# SMDv2.net
KiCad netlist of a schematic drawn in EAGLE
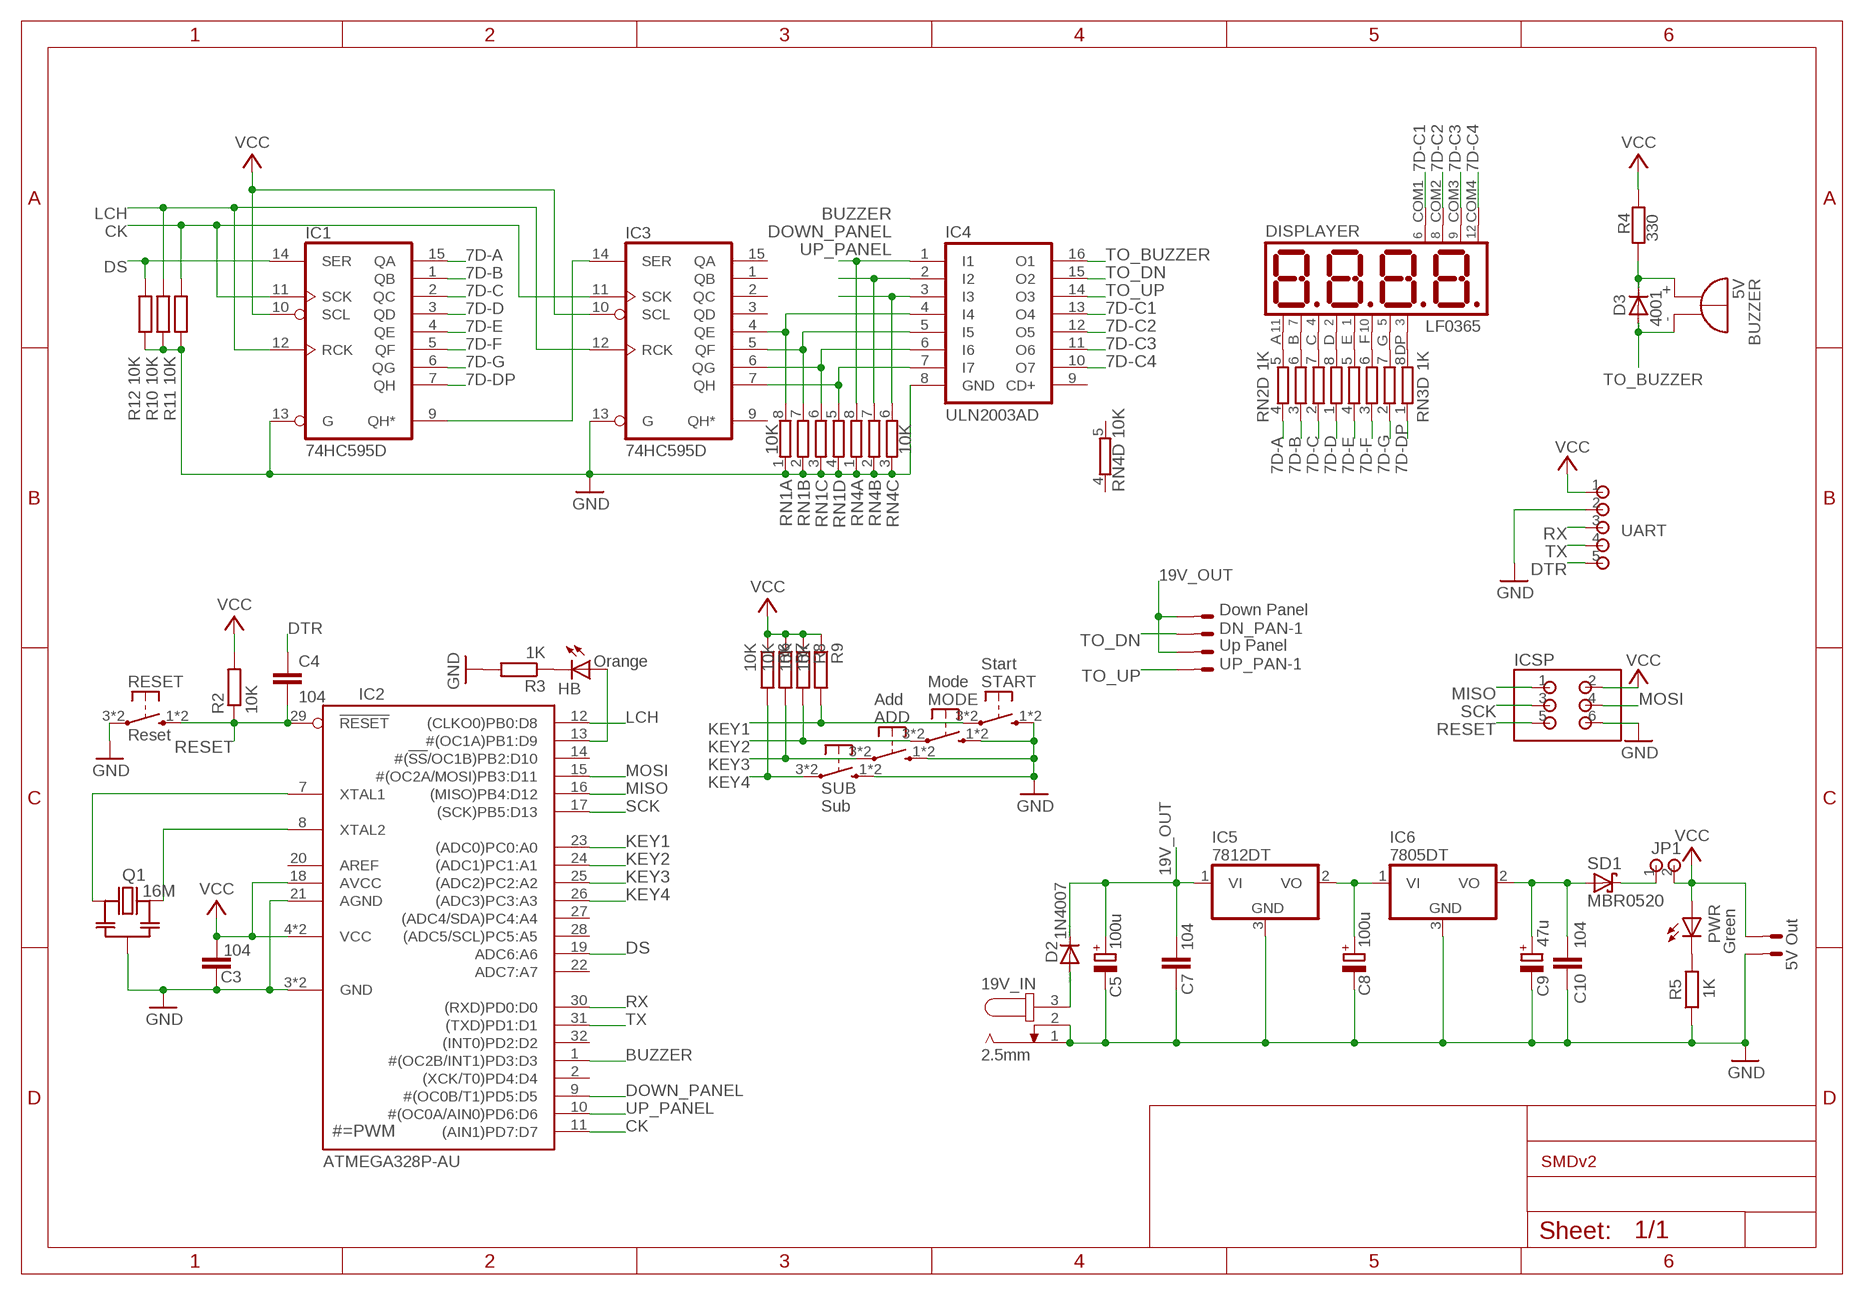
[diagram p0: schematic, sheet 1]

(export (version "E")
  (design (tool "Eeschema 10.0.6"))
  (components
    (comp (ref "5V_OUT")
      (value "5V Out")
      (footprint "eagle-import:L02P")
      (libsource (lib "eagle-import") (part "L02P"))
    )
    (comp (ref "19V_IN")
      (value "2.5mm")
      (footprint "eagle-import:SPC4078")
      (libsource (lib "eagle-import") (part "DC-JACK/2.5MM"))
    )
    (comp (ref "ADD")
      (value "Add")
      (footprint "eagle-import:SW-6_6_3.8MM")
      (libsource (lib "eagle-import") (part "SW-PUSH/663.8MM"))
    )
    (comp (ref "BUZZER")
      (value "5V")
      (footprint "eagle-import:BZ-5V")
      (libsource (lib "eagle-import") (part "BZ-5V"))
    )
    (comp (ref "C3")
      (value "104")
      (footprint "eagle-import:C0805")
      (libsource (lib "eagle-import") (part "C-EUC0805"))
    )
    (comp (ref "C4")
      (value "104")
      (footprint "eagle-import:C0805")
      (libsource (lib "eagle-import") (part "C-EUC0805"))
    )
    (comp (ref "C5")
      (value "100u")
      (footprint "eagle-import:140CLH-0810")
      (libsource (lib "eagle-import") (part "CPOL-EU140CLH-0810"))
    )
    (comp (ref "C7")
      (value "104")
      (footprint "eagle-import:C0805")
      (libsource (lib "eagle-import") (part "C-EUC0805"))
    )
    (comp (ref "C8")
      (value "100u")
      (footprint "eagle-import:SMC_C")
      (libsource (lib "eagle-import") (part "CPOL-EUSMCC"))
    )
    (comp (ref "C9")
      (value "47u")
      (footprint "eagle-import:SMC_C")
      (libsource (lib "eagle-import") (part "CPOL-EUSMCC"))
    )
    (comp (ref "C10")
      (value "104")
      (footprint "eagle-import:C0805")
      (libsource (lib "eagle-import") (part "C-EUC0805"))
    )
    (comp (ref "D2")
      (value "1N4007")
      (footprint "eagle-import:DO-214AC")
      (libsource (lib "eagle-import") (part "DIODE-DO-214AC"))
    )
    (comp (ref "D3")
      (value "4001")
      (footprint "eagle-import:DO-214AC")
      (libsource (lib "eagle-import") (part "DIODE-DO-214AC"))
    )
    (comp (ref "DISPLAYER")
      (value "LF0365")
      (footprint "eagle-import:LF036_")
      (libsource (lib "eagle-import") (part "LF0365"))
    )
    (comp (ref "DN_PAN")
      (value "Down Panel")
      (footprint "eagle-import:L02P")
      (libsource (lib "eagle-import") (part "L02P"))
    )
    (comp (ref "HB")
      (value "Orange")
      (footprint "eagle-import:CHIPLED_1206")
      (libsource (lib "eagle-import") (part "LEDCHIPLED_1206"))
    )
    (comp (ref "IC1")
      (value "74HC595D")
      (footprint "eagle-import:SO16")
      (libsource (lib "eagle-import") (part "74595DHC"))
    )
    (comp (ref "IC2")
      (value "ATMEGA328P-AU")
      (footprint "eagle-import:TQFP32")
      (libsource (lib "eagle-import") (part "ATMEGA328P-AU"))
    )
    (comp (ref "IC3")
      (value "74HC595D")
      (footprint "eagle-import:SO16")
      (libsource (lib "eagle-import") (part "74595DHC"))
    )
    (comp (ref "IC4")
      (value "ULN2003AD")
      (footprint "eagle-import:SO16")
      (libsource (lib "eagle-import") (part "ULN2003AD"))
    )
    (comp (ref "IC5")
      (value "7812DT")
      (footprint "eagle-import:TO252")
      (libsource (lib "eagle-import") (part "78DT12"))
    )
    (comp (ref "IC6")
      (value "7805DT")
      (footprint "eagle-import:TO252")
      (libsource (lib "eagle-import") (part "78DT05"))
    )
    (comp (ref "ICSP")
      (value "PIN-2X3/DIP")
      (footprint "eagle-import:DIP-2.54-2X3")
      (libsource (lib "eagle-import") (part "PIN-2X3/DIP"))
    )
    (comp (ref "JP1")
      (value "PIN-1X2-2.54")
      (footprint "eagle-import:DIP-2.54-1X2")
      (libsource (lib "eagle-import") (part "PIN-1X2-2.54"))
    )
    (comp (ref "MODE")
      (value "Mode")
      (footprint "eagle-import:SW-6_6_3.8MM")
      (libsource (lib "eagle-import") (part "SW-PUSH/663.8MM"))
    )
    (comp (ref "PWR")
      (value "Green")
      (footprint "eagle-import:CHIPLED_1206")
      (libsource (lib "eagle-import") (part "LEDCHIPLED_1206"))
    )
    (comp (ref "Q1")
      (value "16M")
      (footprint "eagle-import:CSTCE")
      (libsource (lib "eagle-import") (part "CERMOSCILL-CSTCE"))
    )
    (comp (ref "R2")
      (value "10K")
      (footprint "eagle-import:R0805")
      (libsource (lib "eagle-import") (part "R-EU_R0805"))
    )
    (comp (ref "R3")
      (value "1K")
      (footprint "eagle-import:R0805")
      (libsource (lib "eagle-import") (part "R-EU_R0805"))
    )
    (comp (ref "R4")
      (value "330")
      (footprint "eagle-import:R0805")
      (libsource (lib "eagle-import") (part "R-EU_R0805"))
    )
    (comp (ref "R5")
      (value "1K")
      (footprint "eagle-import:R0805")
      (libsource (lib "eagle-import") (part "R-EU_R0805"))
    )
    (comp (ref "R6")
      (value "10K")
      (footprint "eagle-import:R0805")
      (libsource (lib "eagle-import") (part "R-EU_R0805"))
    )
    (comp (ref "R7")
      (value "10K")
      (footprint "eagle-import:R0805")
      (libsource (lib "eagle-import") (part "R-EU_R0805"))
    )
    (comp (ref "R8")
      (value "10K")
      (footprint "eagle-import:R0805")
      (libsource (lib "eagle-import") (part "R-EU_R0805"))
    )
    (comp (ref "R9")
      (value "10K")
      (footprint "eagle-import:R0805")
      (libsource (lib "eagle-import") (part "R-EU_R0805"))
    )
    (comp (ref "R10")
      (value "10K")
      (footprint "eagle-import:R0805")
      (libsource (lib "eagle-import") (part "R-EU_R0805"))
    )
    (comp (ref "R11")
      (value "10K")
      (footprint "eagle-import:R0805")
      (libsource (lib "eagle-import") (part "R-EU_R0805"))
    )
    (comp (ref "R12")
      (value "10K")
      (footprint "eagle-import:R0805")
      (libsource (lib "eagle-import") (part "R-EU_R0805"))
    )
    (comp (ref "RESET")
      (value "Reset")
      (footprint "eagle-import:SW-4_4_3.8MM")
      (libsource (lib "eagle-import") (part "SW-PUSH/443.8MM"))
    )
    (comp (ref "RN1")
      (value "10K")
      (footprint "eagle-import:CAY16")
      (libsource (lib "eagle-import") (part "RN4R-CAY16"))
    )
    (comp (ref "RN2")
      (value "1K")
      (footprint "eagle-import:CAY16")
      (libsource (lib "eagle-import") (part "RN4R-CAY16"))
    )
    (comp (ref "RN3")
      (value "1K")
      (footprint "eagle-import:CAY16")
      (libsource (lib "eagle-import") (part "RN4R-CAY16"))
    )
    (comp (ref "RN4")
      (value "10K")
      (footprint "eagle-import:CAY16")
      (libsource (lib "eagle-import") (part "RN4R-CAY16"))
    )
    (comp (ref "SD1")
      (value "MBR0520")
      (footprint "eagle-import:SOD123")
      (libsource (lib "eagle-import") (part "SCHOTTKY"))
    )
    (comp (ref "START")
      (value "Start")
      (footprint "eagle-import:SW-6_6_3.8MM")
      (libsource (lib "eagle-import") (part "SW-PUSH/663.8MM"))
    )
    (comp (ref "SUB")
      (value "Sub")
      (footprint "eagle-import:SW-6_6_3.8MM")
      (libsource (lib "eagle-import") (part "SW-PUSH/663.8MM"))
    )
    (comp (ref "UART")
      (value "PIN-1X5-2.54")
      (footprint "eagle-import:DIP-2.54-1X5")
      (libsource (lib "eagle-import") (part "PIN-1X5-2.54"))
    )
    (comp (ref "UP_PAN")
      (value "Up Panel")
      (footprint "eagle-import:L02P")
      (libsource (lib "eagle-import") (part "L02P"))
    )
  )
  (nets
    (net (code "1") (name "/7D-A") (class "Default")
      (node (ref "IC1") (pin "15") (pinfunction "QA_15") (pintype "tri_state"))
      (node (ref "RN2") (pin "4") (pinfunction "1_4") (pintype "passive"))
    )
    (net (code "2") (name "/7D-B") (class "Default")
      (node (ref "IC1") (pin "1") (pinfunction "QB_1") (pintype "tri_state"))
      (node (ref "RN2") (pin "3") (pinfunction "1_3") (pintype "passive"))
    )
    (net (code "3") (name "/7D-C") (class "Default")
      (node (ref "IC1") (pin "2") (pinfunction "QC_2") (pintype "tri_state"))
      (node (ref "RN2") (pin "2") (pinfunction "1_2") (pintype "passive"))
    )
    (net (code "4") (name "/7D-C1") (class "Default")
      (node (ref "DISPLAYER") (pin "COM1") (pinfunction "COM1_COM1") (pintype "passive"))
      (node (ref "IC4") (pin "13") (pinfunction "O4_13") (pintype "open_collector"))
    )
    (net (code "5") (name "/7D-C2") (class "Default")
      (node (ref "DISPLAYER") (pin "COM2") (pinfunction "COM2_COM2") (pintype "passive"))
      (node (ref "IC4") (pin "12") (pinfunction "O5_12") (pintype "open_collector"))
    )
    (net (code "6") (name "/7D-C3") (class "Default")
      (node (ref "DISPLAYER") (pin "COM3") (pinfunction "COM3_COM3") (pintype "passive"))
      (node (ref "IC4") (pin "11") (pinfunction "O6_11") (pintype "open_collector"))
    )
    (net (code "7") (name "/7D-C4") (class "Default")
      (node (ref "DISPLAYER") (pin "COM4") (pinfunction "COM4_COM4") (pintype "passive"))
      (node (ref "IC4") (pin "10") (pinfunction "O7_10") (pintype "open_collector"))
    )
    (net (code "8") (name "/7D-D") (class "Default")
      (node (ref "IC1") (pin "3") (pinfunction "QD_3") (pintype "tri_state"))
      (node (ref "RN2") (pin "1") (pinfunction "1_1") (pintype "passive"))
    )
    (net (code "9") (name "/7D-DP") (class "Default")
      (node (ref "IC1") (pin "7") (pinfunction "QH_7") (pintype "tri_state"))
      (node (ref "RN3") (pin "1") (pinfunction "1_1") (pintype "passive"))
    )
    (net (code "10") (name "/7D-E") (class "Default")
      (node (ref "IC1") (pin "4") (pinfunction "QE_4") (pintype "tri_state"))
      (node (ref "RN3") (pin "4") (pinfunction "1_4") (pintype "passive"))
    )
    (net (code "11") (name "/7D-F") (class "Default")
      (node (ref "IC1") (pin "5") (pinfunction "QF_5") (pintype "tri_state"))
      (node (ref "RN3") (pin "3") (pinfunction "1_3") (pintype "passive"))
    )
    (net (code "12") (name "/7D-G") (class "Default")
      (node (ref "IC1") (pin "6") (pinfunction "QG_6") (pintype "tri_state"))
      (node (ref "RN3") (pin "2") (pinfunction "1_2") (pintype "passive"))
    )
    (net (code "13") (name "/19V_OUT") (class "Default")
      (node (ref "C5") (pin "+") (pinfunction "+_+") (pintype "passive"))
      (node (ref "C7") (pin "1") (pinfunction "1_1") (pintype "passive"))
      (node (ref "D2") (pin "C") (pinfunction "C_C") (pintype "passive"))
      (node (ref "DN_PAN") (pin "2") (pinfunction "S_2") (pintype "passive"))
      (node (ref "IC5") (pin "1") (pinfunction "VI_1") (pintype "input"))
      (node (ref "UP_PAN") (pin "2") (pinfunction "S_2") (pintype "passive"))
    )
    (net (code "14") (name "/BUZZER") (class "Default")
      (node (ref "IC2") (pin "1") (pinfunction "#(OC2B/INT1)PD3:D3_1") (pintype "bidirectional"))
      (node (ref "IC4") (pin "1") (pinfunction "I1_1") (pintype "input"))
      (node (ref "RN4") (pin "8") (pinfunction "2_8") (pintype "passive"))
    )
    (net (code "15") (name "/CK") (class "Default")
      (node (ref "IC1") (pin "11") (pinfunction "SCK_11") (pintype "input"))
      (node (ref "IC2") (pin "11") (pinfunction "(AIN1)PD7:D7_11") (pintype "bidirectional"))
      (node (ref "IC3") (pin "11") (pinfunction "SCK_11") (pintype "input"))
      (node (ref "R11") (pin "2") (pinfunction "2_2") (pintype "passive"))
    )
    (net (code "16") (name "/DOWN_PANEL") (class "Default")
      (node (ref "IC2") (pin "9") (pinfunction "#(OC0B/T1)PD5:D5_9") (pintype "bidirectional"))
      (node (ref "IC4") (pin "2") (pinfunction "I2_2") (pintype "input"))
      (node (ref "RN4") (pin "7") (pinfunction "2_7") (pintype "passive"))
    )
    (net (code "17") (name "/DS") (class "Default")
      (node (ref "IC1") (pin "14") (pinfunction "SER_14") (pintype "input"))
      (node (ref "IC2") (pin "19") (pinfunction "ADC6:A6_19") (pintype "bidirectional"))
      (node (ref "R12") (pin "2") (pinfunction "2_2") (pintype "passive"))
    )
    (net (code "18") (name "/DTR") (class "Default")
      (node (ref "C4") (pin "1") (pinfunction "1_1") (pintype "passive"))
      (node (ref "UART") (pin "5") (pinfunction "5_5") (pintype "passive"))
    )
    (net (code "19") (name "/KEY1") (class "Default")
      (node (ref "IC2") (pin "23") (pinfunction "(ADC0)PC0:A0_23") (pintype "bidirectional"))
      (node (ref "R9") (pin "2") (pinfunction "2_2") (pintype "passive"))
      (node (ref "START") (pin "3") (pinfunction "P_3") (pintype "passive"))
      (node (ref "START") (pin "4") (pinfunction "P_4") (pintype "passive"))
    )
    (net (code "20") (name "/KEY2") (class "Default")
      (node (ref "IC2") (pin "24") (pinfunction "(ADC1)PC1:A1_24") (pintype "bidirectional"))
      (node (ref "MODE") (pin "3") (pinfunction "P_3") (pintype "passive"))
      (node (ref "MODE") (pin "4") (pinfunction "P_4") (pintype "passive"))
      (node (ref "R8") (pin "2") (pinfunction "2_2") (pintype "passive"))
    )
    (net (code "21") (name "/KEY3") (class "Default")
      (node (ref "ADD") (pin "3") (pinfunction "P_3") (pintype "passive"))
      (node (ref "ADD") (pin "4") (pinfunction "P_4") (pintype "passive"))
      (node (ref "IC2") (pin "25") (pinfunction "(ADC2)PC2:A2_25") (pintype "bidirectional"))
      (node (ref "R7") (pin "2") (pinfunction "2_2") (pintype "passive"))
    )
    (net (code "22") (name "/KEY4") (class "Default")
      (node (ref "IC2") (pin "26") (pinfunction "(ADC3)PC3:A3_26") (pintype "bidirectional"))
      (node (ref "R6") (pin "2") (pinfunction "2_2") (pintype "passive"))
      (node (ref "SUB") (pin "3") (pinfunction "P_3") (pintype "passive"))
      (node (ref "SUB") (pin "4") (pinfunction "P_4") (pintype "passive"))
    )
    (net (code "23") (name "/LCH") (class "Default")
      (node (ref "IC1") (pin "12") (pinfunction "RCK_12") (pintype "input"))
      (node (ref "IC2") (pin "12") (pinfunction "(CLKO0)PB0:D8_12") (pintype "bidirectional"))
      (node (ref "IC3") (pin "12") (pinfunction "RCK_12") (pintype "input"))
      (node (ref "R10") (pin "2") (pinfunction "2_2") (pintype "passive"))
    )
    (net (code "24") (name "/MISO") (class "Default")
      (node (ref "IC2") (pin "16") (pinfunction "(MISO)PB4:D12_16") (pintype "bidirectional"))
      (node (ref "ICSP") (pin "1") (pinfunction "1_1") (pintype "passive"))
    )
    (net (code "25") (name "/MOSI") (class "Default")
      (node (ref "IC2") (pin "15") (pinfunction "#(OC2A/MOSI)PB3:D11_15") (pintype "bidirectional"))
      (node (ref "ICSP") (pin "4") (pinfunction "4_4") (pintype "passive"))
    )
    (net (code "26") (name "/RESET") (class "Default")
      (node (ref "C4") (pin "2") (pinfunction "2_2") (pintype "passive"))
      (node (ref "IC2") (pin "29") (pinfunction "~{RESET}_29") (pintype "input"))
      (node (ref "ICSP") (pin "5") (pinfunction "5_5") (pintype "passive"))
      (node (ref "R2") (pin "1") (pinfunction "1_1") (pintype "passive"))
      (node (ref "RESET") (pin "1") (pinfunction "S_1") (pintype "passive"))
      (node (ref "RESET") (pin "2") (pinfunction "S_2") (pintype "passive"))
    )
    (net (code "27") (name "/RX") (class "Default")
      (node (ref "IC2") (pin "30") (pinfunction "(RXD)PD0:D0_30") (pintype "bidirectional"))
      (node (ref "UART") (pin "3") (pinfunction "3_3") (pintype "passive"))
    )
    (net (code "28") (name "/SCK") (class "Default")
      (node (ref "IC2") (pin "17") (pinfunction "(SCK)PB5:D13_17") (pintype "bidirectional"))
      (node (ref "ICSP") (pin "3") (pinfunction "3_3") (pintype "passive"))
    )
    (net (code "29") (name "/TO_BUZZER") (class "Default")
      (node (ref "BUZZER") (pin "-") (pinfunction "-_-") (pintype "passive"))
      (node (ref "D3") (pin "A") (pinfunction "A_A") (pintype "passive"))
      (node (ref "IC4") (pin "16") (pinfunction "O1_16") (pintype "open_collector"))
    )
    (net (code "30") (name "/TO_DN") (class "Default")
      (node (ref "DN_PAN") (pin "1") (pinfunction "S_1") (pintype "passive"))
      (node (ref "IC4") (pin "15") (pinfunction "O2_15") (pintype "open_collector"))
    )
    (net (code "31") (name "/TO_UP") (class "Default")
      (node (ref "IC4") (pin "14") (pinfunction "O3_14") (pintype "open_collector"))
      (node (ref "UP_PAN") (pin "1") (pinfunction "S_1") (pintype "passive"))
    )
    (net (code "32") (name "/TX") (class "Default")
      (node (ref "IC2") (pin "31") (pinfunction "(TXD)PD1:D1_31") (pintype "bidirectional"))
      (node (ref "UART") (pin "4") (pinfunction "4_4") (pintype "passive"))
    )
    (net (code "33") (name "/UP_PANEL") (class "Default")
      (node (ref "IC2") (pin "10") (pinfunction "#(OC0A/AIN0)PD6:D6_10") (pintype "bidirectional"))
      (node (ref "IC4") (pin "3") (pinfunction "I3_3") (pintype "input"))
      (node (ref "RN4") (pin "6") (pinfunction "2_6") (pintype "passive"))
    )
    (net (code "34") (name "GND") (class "Default")
      (node (ref "19V_IN") (pin "1") (pinfunction "1_1") (pintype "passive"))
      (node (ref "19V_IN") (pin "2") (pinfunction "2_2") (pintype "passive"))
      (node (ref "5V_OUT") (pin "1") (pinfunction "S_1") (pintype "passive"))
      (node (ref "ADD") (pin "1") (pinfunction "S_1") (pintype "passive"))
      (node (ref "ADD") (pin "2") (pinfunction "S_2") (pintype "passive"))
      (node (ref "C10") (pin "2") (pinfunction "2_2") (pintype "passive"))
      (node (ref "C3") (pin "1") (pinfunction "1_1") (pintype "passive"))
      (node (ref "C5") (pin "-") (pinfunction "-_-") (pintype "passive"))
      (node (ref "C7") (pin "2") (pinfunction "2_2") (pintype "passive"))
      (node (ref "C8") (pin "-") (pinfunction "-_-") (pintype "passive"))
      (node (ref "C9") (pin "-") (pinfunction "-_-") (pintype "passive"))
      (node (ref "IC1") (pin "13") (pinfunction "G_13") (pintype "input"))
      (node (ref "IC2") (pin "21") (pinfunction "AGND_21") (pintype "passive"))
      (node (ref "IC2") (pin "3") (pinfunction "GND_3") (pintype "power_in"))
      (node (ref "IC2") (pin "5") (pinfunction "GND_5") (pintype "power_in"))
      (node (ref "IC3") (pin "13") (pinfunction "G_13") (pintype "input"))
      (node (ref "IC4") (pin "8") (pinfunction "GND_8") (pintype "power_in"))
      (node (ref "IC5") (pin "3") (pinfunction "GND_3") (pintype "passive"))
      (node (ref "IC6") (pin "3") (pinfunction "GND_3") (pintype "passive"))
      (node (ref "ICSP") (pin "6") (pinfunction "6_6") (pintype "passive"))
      (node (ref "MODE") (pin "1") (pinfunction "S_1") (pintype "passive"))
      (node (ref "MODE") (pin "2") (pinfunction "S_2") (pintype "passive"))
      (node (ref "Q1") (pin "2") (pinfunction "GND_2") (pintype "bidirectional"))
      (node (ref "R10") (pin "1") (pinfunction "1_1") (pintype "passive"))
      (node (ref "R11") (pin "1") (pinfunction "1_1") (pintype "passive"))
      (node (ref "R12") (pin "1") (pinfunction "1_1") (pintype "passive"))
      (node (ref "R3") (pin "2") (pinfunction "2_2") (pintype "passive"))
      (node (ref "R5") (pin "1") (pinfunction "1_1") (pintype "passive"))
      (node (ref "RESET") (pin "3") (pinfunction "P_3") (pintype "passive"))
      (node (ref "RESET") (pin "4") (pinfunction "P_4") (pintype "passive"))
      (node (ref "RN1") (pin "1") (pinfunction "1_1") (pintype "passive"))
      (node (ref "RN1") (pin "2") (pinfunction "1_2") (pintype "passive"))
      (node (ref "RN1") (pin "3") (pinfunction "1_3") (pintype "passive"))
      (node (ref "RN1") (pin "4") (pinfunction "1_4") (pintype "passive"))
      (node (ref "RN4") (pin "1") (pinfunction "1_1") (pintype "passive"))
      (node (ref "RN4") (pin "2") (pinfunction "1_2") (pintype "passive"))
      (node (ref "RN4") (pin "3") (pinfunction "1_3") (pintype "passive"))
      (node (ref "START") (pin "1") (pinfunction "S_1") (pintype "passive"))
      (node (ref "START") (pin "2") (pinfunction "S_2") (pintype "passive"))
      (node (ref "SUB") (pin "1") (pinfunction "S_1") (pintype "passive"))
      (node (ref "SUB") (pin "2") (pinfunction "S_2") (pintype "passive"))
      (node (ref "UART") (pin "2") (pinfunction "2_2") (pintype "passive"))
    )
    (net (code "35") (name "Net-(19V_IN-Pad3)") (class "Default")
      (node (ref "19V_IN") (pin "3") (pinfunction "3_3") (pintype "passive"))
      (node (ref "D2") (pin "A") (pinfunction "A_A") (pintype "passive"))
    )
    (net (code "36") (name "Net-(BUZZER-Pad+)") (class "Default")
      (node (ref "BUZZER") (pin "+") (pinfunction "+_+") (pintype "passive"))
      (node (ref "D3") (pin "C") (pinfunction "C_C") (pintype "passive"))
      (node (ref "R4") (pin "1") (pinfunction "1_1") (pintype "passive"))
    )
    (net (code "37") (name "Net-(HB-PadC)") (class "Default")
      (node (ref "HB") (pin "C") (pinfunction "C_C") (pintype "passive"))
      (node (ref "R3") (pin "1") (pinfunction "1_1") (pintype "passive"))
    )
    (net (code "38") (name "Net-(IC1A-QH*)") (class "Default")
      (node (ref "IC1") (pin "9") (pinfunction "QH*_9") (pintype "tri_state"))
      (node (ref "IC3") (pin "14") (pinfunction "SER_14") (pintype "input"))
    )
    (net (code "39") (name "Net-(IC2-#(OC1A)PB1:D9)") (class "Default")
      (node (ref "HB") (pin "A") (pinfunction "A_A") (pintype "passive"))
      (node (ref "IC2") (pin "13") (pinfunction "#(OC1A)PB1:D9_13") (pintype "bidirectional"))
    )
    (net (code "40") (name "Net-(IC2-XTAL1)") (class "Default")
      (node (ref "IC2") (pin "7") (pinfunction "XTAL1_7") (pintype "bidirectional"))
      (node (ref "Q1") (pin "1") (pinfunction "IN_1") (pintype "bidirectional"))
    )
    (net (code "41") (name "Net-(IC2-XTAL2)") (class "Default")
      (node (ref "IC2") (pin "8") (pinfunction "XTAL2_8") (pintype "bidirectional"))
      (node (ref "Q1") (pin "3") (pinfunction "OUT_3") (pintype "bidirectional"))
    )
    (net (code "42") (name "Net-(IC3A-QE)") (class "Default")
      (node (ref "IC3") (pin "4") (pinfunction "QE_4") (pintype "tri_state"))
      (node (ref "IC4") (pin "4") (pinfunction "I4_4") (pintype "input"))
      (node (ref "RN1") (pin "8") (pinfunction "2_8") (pintype "passive"))
    )
    (net (code "43") (name "Net-(IC3A-QF)") (class "Default")
      (node (ref "IC3") (pin "5") (pinfunction "QF_5") (pintype "tri_state"))
      (node (ref "IC4") (pin "5") (pinfunction "I5_5") (pintype "input"))
      (node (ref "RN1") (pin "7") (pinfunction "2_7") (pintype "passive"))
    )
    (net (code "44") (name "Net-(IC3A-QG)") (class "Default")
      (node (ref "IC3") (pin "6") (pinfunction "QG_6") (pintype "tri_state"))
      (node (ref "IC4") (pin "6") (pinfunction "I6_6") (pintype "input"))
      (node (ref "RN1") (pin "6") (pinfunction "2_6") (pintype "passive"))
    )
    (net (code "45") (name "Net-(IC3A-QH)") (class "Default")
      (node (ref "IC3") (pin "7") (pinfunction "QH_7") (pintype "tri_state"))
      (node (ref "IC4") (pin "7") (pinfunction "I7_7") (pintype "input"))
      (node (ref "RN1") (pin "5") (pinfunction "2_5") (pintype "passive"))
    )
    (net (code "46") (name "Net-(IC5-VO)") (class "Default")
      (node (ref "C8") (pin "+") (pinfunction "+_+") (pintype "passive"))
      (node (ref "IC5") (pin "2") (pinfunction "VO_2") (pintype "passive"))
      (node (ref "IC6") (pin "1") (pinfunction "VI_1") (pintype "input"))
    )
    (net (code "47") (name "Net-(IC6-VO)") (class "Default")
      (node (ref "C10") (pin "1") (pinfunction "1_1") (pintype "passive"))
      (node (ref "C9") (pin "+") (pinfunction "+_+") (pintype "passive"))
      (node (ref "IC6") (pin "2") (pinfunction "VO_2") (pintype "passive"))
      (node (ref "SD1") (pin "A") (pinfunction "A_A") (pintype "passive"))
    )
    (net (code "48") (name "Net-(JP1-Pad1)") (class "Default")
      (node (ref "JP1") (pin "1") (pinfunction "1_1") (pintype "passive"))
      (node (ref "SD1") (pin "K") (pinfunction "K_K") (pintype "passive"))
    )
    (net (code "49") (name "Net-(PWR-PadC)") (class "Default")
      (node (ref "PWR") (pin "C") (pinfunction "C_C") (pintype "passive"))
      (node (ref "R5") (pin "2") (pinfunction "2_2") (pintype "passive"))
    )
    (net (code "50") (name "Net-(RN2A-2)") (class "Default")
      (node (ref "DISPLAYER") (pin "D") (pinfunction "D_D") (pintype "input"))
      (node (ref "RN2") (pin "8") (pinfunction "2_8") (pintype "passive"))
    )
    (net (code "51") (name "Net-(RN2B-2)") (class "Default")
      (node (ref "DISPLAYER") (pin "C") (pinfunction "C_C") (pintype "input"))
      (node (ref "RN2") (pin "7") (pinfunction "2_7") (pintype "passive"))
    )
    (net (code "52") (name "Net-(RN2C-2)") (class "Default")
      (node (ref "DISPLAYER") (pin "B") (pinfunction "B_B") (pintype "input"))
      (node (ref "RN2") (pin "6") (pinfunction "2_6") (pintype "passive"))
    )
    (net (code "53") (name "Net-(RN2D-2)") (class "Default")
      (node (ref "DISPLAYER") (pin "A") (pinfunction "A_A") (pintype "input"))
      (node (ref "RN2") (pin "5") (pinfunction "2_5") (pintype "passive"))
    )
    (net (code "54") (name "Net-(RN3A-2)") (class "Default")
      (node (ref "DISPLAYER") (pin "DP") (pinfunction "DP_DP") (pintype "input"))
      (node (ref "RN3") (pin "8") (pinfunction "2_8") (pintype "passive"))
    )
    (net (code "55") (name "Net-(RN3B-2)") (class "Default")
      (node (ref "DISPLAYER") (pin "G") (pinfunction "G_G") (pintype "input"))
      (node (ref "RN3") (pin "7") (pinfunction "2_7") (pintype "passive"))
    )
    (net (code "56") (name "Net-(RN3C-2)") (class "Default")
      (node (ref "DISPLAYER") (pin "F") (pinfunction "F_F") (pintype "input"))
      (node (ref "RN3") (pin "6") (pinfunction "2_6") (pintype "passive"))
    )
    (net (code "57") (name "Net-(RN3D-2)") (class "Default")
      (node (ref "DISPLAYER") (pin "E") (pinfunction "E_E") (pintype "input"))
      (node (ref "RN3") (pin "5") (pinfunction "2_5") (pintype "passive"))
    )
    (net (code "58") (name "VCC") (class "Default")
      (node (ref "5V_OUT") (pin "2") (pinfunction "S_2") (pintype "passive"))
      (node (ref "C3") (pin "2") (pinfunction "2_2") (pintype "passive"))
      (node (ref "IC1") (pin "10") (pinfunction "SCL_10") (pintype "input"))
      (node (ref "IC2") (pin "18") (pinfunction "AVCC_18") (pintype "passive"))
      (node (ref "IC2") (pin "4") (pinfunction "VCC_4") (pintype "power_in"))
      (node (ref "IC2") (pin "6") (pinfunction "VCC_6") (pintype "power_in"))
      (node (ref "IC3") (pin "10") (pinfunction "SCL_10") (pintype "input"))
      (node (ref "ICSP") (pin "2") (pinfunction "2_2") (pintype "passive"))
      (node (ref "JP1") (pin "2") (pinfunction "2_2") (pintype "passive"))
      (node (ref "PWR") (pin "A") (pinfunction "A_A") (pintype "passive"))
      (node (ref "R2") (pin "2") (pinfunction "2_2") (pintype "passive"))
      (node (ref "R4") (pin "2") (pinfunction "2_2") (pintype "passive"))
      (node (ref "R6") (pin "1") (pinfunction "1_1") (pintype "passive"))
      (node (ref "R7") (pin "1") (pinfunction "1_1") (pintype "passive"))
      (node (ref "R8") (pin "1") (pinfunction "1_1") (pintype "passive"))
      (node (ref "R9") (pin "1") (pinfunction "1_1") (pintype "passive"))
      (node (ref "UART") (pin "1") (pinfunction "1_1") (pintype "passive"))
    )
    (net (code "59") (name "unconnected-(IC2-#(~{SS}{slash}OC1B)PB2:D10-Pad14)") (class "Default")
      (node (ref "IC2") (pin "14") (pinfunction "#(~{SS}/OC1B)PB2:D10_14") (pintype "bidirectional"))
    )
    (net (code "60") (name "unconnected-(IC2-(ADC4{slash}SDA)PC4:A4-Pad27)") (class "Default")
      (node (ref "IC2") (pin "27") (pinfunction "(ADC4/SDA)PC4:A4_27") (pintype "bidirectional"))
    )
    (net (code "61") (name "unconnected-(IC2-(ADC5{slash}SCL)PC5:A5-Pad28)") (class "Default")
      (node (ref "IC2") (pin "28") (pinfunction "(ADC5/SCL)PC5:A5_28") (pintype "bidirectional"))
    )
    (net (code "62") (name "unconnected-(IC2-(INT0)PD2:D2-Pad32)") (class "Default")
      (node (ref "IC2") (pin "32") (pinfunction "(INT0)PD2:D2_32") (pintype "bidirectional"))
    )
    (net (code "63") (name "unconnected-(IC2-(XCK{slash}T0)PD4:D4-Pad2)") (class "Default")
      (node (ref "IC2") (pin "2") (pinfunction "(XCK/T0)PD4:D4_2") (pintype "bidirectional"))
    )
    (net (code "64") (name "unconnected-(IC2-ADC7:A7-Pad22)") (class "Default")
      (node (ref "IC2") (pin "22") (pinfunction "ADC7:A7_22") (pintype "bidirectional"))
    )
    (net (code "65") (name "unconnected-(IC2-AREF-Pad20)") (class "Default")
      (node (ref "IC2") (pin "20") (pinfunction "AREF_20") (pintype "passive"))
    )
    (net (code "66") (name "unconnected-(IC3A-QA-Pad15)") (class "Default")
      (node (ref "IC3") (pin "15") (pinfunction "QA_15") (pintype "tri_state"))
    )
    (net (code "67") (name "unconnected-(IC3A-QB-Pad1)") (class "Default")
      (node (ref "IC3") (pin "1") (pinfunction "QB_1") (pintype "tri_state"))
    )
    (net (code "68") (name "unconnected-(IC3A-QC-Pad2)") (class "Default")
      (node (ref "IC3") (pin "2") (pinfunction "QC_2") (pintype "tri_state"))
    )
    (net (code "69") (name "unconnected-(IC3A-QD-Pad3)") (class "Default")
      (node (ref "IC3") (pin "3") (pinfunction "QD_3") (pintype "tri_state"))
    )
    (net (code "70") (name "unconnected-(IC3A-QH*-Pad9)") (class "Default")
      (node (ref "IC3") (pin "9") (pinfunction "QH*_9") (pintype "tri_state"))
    )
    (net (code "71") (name "unconnected-(IC4-CD+-Pad9)") (class "Default")
      (node (ref "IC4") (pin "9") (pinfunction "CD+_9") (pintype "passive"))
    )
    (net (code "72") (name "unconnected-(RN4D-1-Pad4)") (class "Default")
      (node (ref "RN4") (pin "4") (pinfunction "1_4") (pintype "passive"))
    )
    (net (code "73") (name "unconnected-(RN4D-2-Pad5)") (class "Default")
      (node (ref "RN4") (pin "5") (pinfunction "2_5") (pintype "passive"))
    )
  )
)
